# Sheet1.net
KiCad netlist of a schematic drawn in Altium Designer
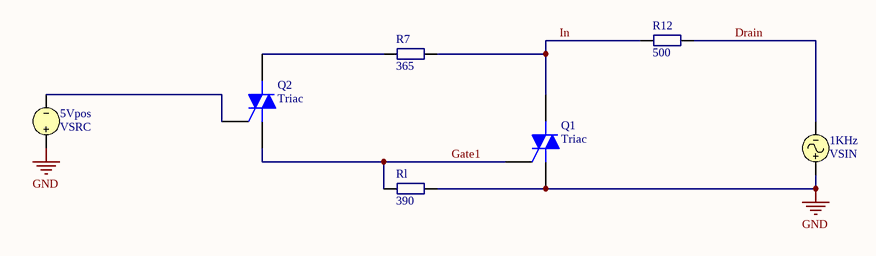
[diagram p0: Sheet1.SchDoc]

(export (version "E")
  (design (tool "Eeschema 10.0.6"))
  (components
    (comp (ref "1KHz")
      (value "VSIN")
      (description "Sinusoidal Voltage Source")
      (fields (field (name "PUBLISHER") "Altium Limited"))
      (libsource (lib "Simulation Sources") (part "VSIN"))
    )
    (comp (ref "5Vpos")
      (value "VSRC")
      (description "Voltage Source")
      (fields (field (name "PUBLISHER") "Altium Limited"))
      (libsource (lib "Simulation Sources") (part "VSRC"))
    )
    (comp (ref "Q1")
      (value "Triac")
      (footprint "369-03")
      (description "Silicon Bidirectional Triode Thyristor")
      (fields (field (name "PUBLISHER") "Altium Limited"))
      (libsource (lib "Miscellaneous Devices") (part "Triac"))
    )
    (comp (ref "Q2")
      (value "Triac")
      (footprint "369-03")
      (description "Silicon Bidirectional Triode Thyristor")
      (fields (field (name "PUBLISHER") "Altium Limited"))
      (libsource (lib "Miscellaneous Devices") (part "Triac"))
    )
    (comp (ref "R7")
      (value "365")
      (footprint "J1-0603")
      (description "Resistor")
      (fields (field (name "PUBLISHER") "Altium Limited"))
      (libsource (lib "LockLib") (part "Res_SMD"))
    )
    (comp (ref "R12")
      (value "500")
      (footprint "J1-0603")
      (description "Resistor")
      (fields (field (name "PUBLISHER") "Altium Limited"))
      (libsource (lib "LockLib") (part "Res_SMD"))
    )
    (comp (ref "Rl")
      (value "390")
      (footprint "J1-0603")
      (description "Resistor")
      (fields (field (name "PUBLISHER") "Altium Limited"))
      (libsource (lib "LockLib") (part "Res_SMD"))
    )
  )
  (nets
    (net (code "1") (name "/Drain") (class "Default")
      (node (ref "1KHz") (pin "2") (pinfunction "2_2") (pintype "passive"))
      (node (ref "R12") (pin "1") (pinfunction "1_1") (pintype "passive"))
    )
    (net (code "2") (name "/Gate1") (class "Default")
      (node (ref "Q1") (pin "3") (pinfunction "G_3") (pintype "passive"))
      (node (ref "Q2") (pin "1") (pinfunction "M1_1") (pintype "passive"))
      (node (ref "Rl") (pin "2") (pinfunction "2_2") (pintype "passive"))
    )
    (net (code "3") (name "/In") (class "Default")
      (node (ref "Q1") (pin "2") (pinfunction "M2_2") (pintype "passive"))
      (node (ref "R12") (pin "2") (pinfunction "2_2") (pintype "passive"))
      (node (ref "R7") (pin "1") (pinfunction "1_1") (pintype "passive"))
    )
    (net (code "4") (name "GND") (class "Default")
      (node (ref "1KHz") (pin "1") (pinfunction "1_1") (pintype "passive"))
      (node (ref "5Vpos") (pin "1") (pinfunction "1_1") (pintype "passive"))
      (node (ref "Q1") (pin "1") (pinfunction "M1_1") (pintype "passive"))
      (node (ref "Rl") (pin "1") (pinfunction "1_1") (pintype "passive"))
    )
    (net (code "5") (name "Net-(Q2-G)") (class "Default")
      (node (ref "5Vpos") (pin "2") (pinfunction "2_2") (pintype "passive"))
      (node (ref "Q2") (pin "3") (pinfunction "G_3") (pintype "passive"))
    )
    (net (code "6") (name "Net-(Q2-M2)") (class "Default")
      (node (ref "Q2") (pin "2") (pinfunction "M2_2") (pintype "passive"))
      (node (ref "R7") (pin "2") (pinfunction "2_2") (pintype "passive"))
    )
  )
)
